# superlna.net
KiCad netlist of a schematic drawn in EAGLE
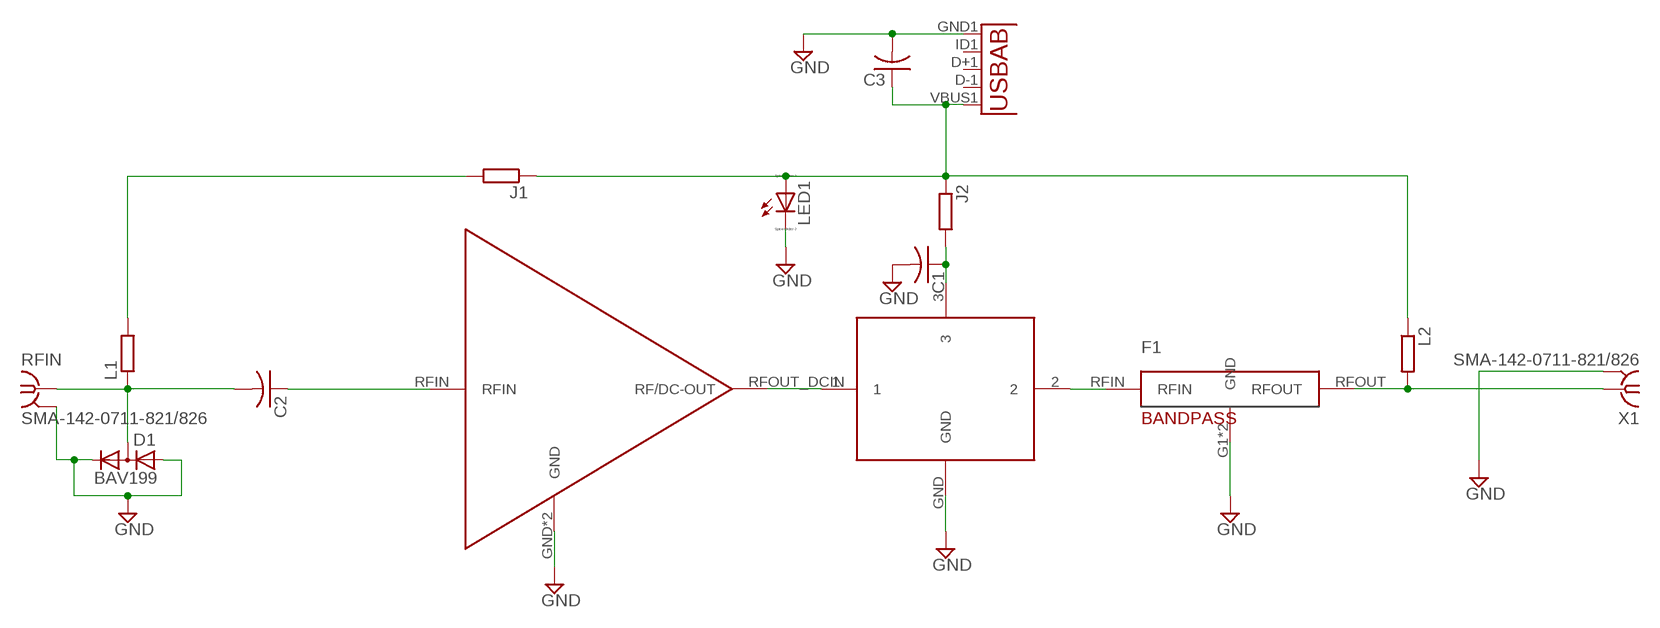
[diagram p0: schematic, sheet 1]

(export (version "E")
  (design (tool "Eeschema 10.0.6"))
  (components
    (comp (ref "C1")
      (value "C-USC0402")
      (footprint "eagle-import:C0402")
      (libsource (lib "eagle-import") (part "C-USC0402"))
    )
    (comp (ref "C2")
      (value "C-USC0402")
      (footprint "eagle-import:C0402")
      (libsource (lib "eagle-import") (part "C-USC0402"))
    )
    (comp (ref "C3")
      (value "C-USC0402")
      (footprint "eagle-import:C0402")
      (libsource (lib "eagle-import") (part "C-USC0402"))
    )
    (comp (ref "D1")
      (value "BAV199")
      (footprint "eagle-import:SOT23")
      (libsource (lib "eagle-import") (part "BAV199"))
    )
    (comp (ref "F1")
      (value "BANDPASS")
      (footprint "eagle-import:FV1206")
      (libsource (lib "eagle-import") (part "BANDPASS"))
    )
    (comp (ref "J1")
      (value "R-EU_R0805")
      (footprint "eagle-import:R0805")
      (libsource (lib "eagle-import") (part "R-EU_R0805"))
    )
    (comp (ref "J2")
      (value "R-EU_R0805")
      (footprint "eagle-import:R0805")
      (libsource (lib "eagle-import") (part "R-EU_R0805"))
    )
    (comp (ref "L1")
      (value "R-EU_R0805")
      (footprint "eagle-import:R0805")
      (libsource (lib "eagle-import") (part "R-EU_R0805"))
    )
    (comp (ref "L2")
      (value "R-EU_R0805")
      (footprint "eagle-import:R0805")
      (libsource (lib "eagle-import") (part "R-EU_R0805"))
    )
    (comp (ref "LED1")
      (value "LED_ESML0603")
      (footprint "eagle-import:LED_SML0603")
      (libsource (lib "eagle-import") (part "LED_ESML0603"))
    )
    (comp (ref "LNA")
      (value "AMP")
      (footprint "eagle-import:SOC-343")
      (libsource (lib "eagle-import") (part "AMP"))
    )
    (comp (ref "POWER")
      (value "USB\"\"")
      (footprint "eagle-import:USB-MICRO-SMD")
      (libsource (lib "eagle-import") (part "USB{dblquote}{dblquote}"))
    )
    (comp (ref "RFIN")
      (value "SMA-142-0711-821/826")
      (footprint "eagle-import:J502-ND-142-0711-821_826")
      (fields (field (name "MF") "JOHNSON COMPONENTS") (field (name "MPN") "142-0711-821"))
      (libsource (lib "eagle-import") (part "SMA-142-0711-821/826"))
    )
    (comp (ref "U1")
      (value "BIASTEE")
      (footprint "eagle-import:GU1414")
      (libsource (lib "eagle-import") (part "BIASTEE"))
    )
    (comp (ref "X1")
      (value "SMA-142-0711-821/826")
      (footprint "eagle-import:J502-ND-142-0711-821_826")
      (fields (field (name "MF") "JOHNSON COMPONENTS") (field (name "MPN") "142-0711-821"))
      (libsource (lib "eagle-import") (part "SMA-142-0711-821/826"))
    )
  )
  (nets
    (net (code "1") (name "GND") (class "Default")
      (node (ref "C1") (pin "2") (pinfunction "2_2") (pintype "passive"))
      (node (ref "C3") (pin "2") (pinfunction "2_2") (pintype "passive"))
      (node (ref "D1") (pin "1") (pinfunction "A_1") (pintype "passive"))
      (node (ref "D1") (pin "2") (pinfunction "C_2") (pintype "passive"))
      (node (ref "F1") (pin "G1") (pinfunction "GND_G1") (pintype "bidirectional"))
      (node (ref "F1") (pin "G2") (pinfunction "GND_G2") (pintype "bidirectional"))
      (node (ref "LED1") (pin "C") (pinfunction "C_C") (pintype "passive"))
      (node (ref "LNA") (pin "GND") (pinfunction "GND_GND") (pintype "bidirectional"))
      (node (ref "LNA") (pin "GND1") (pinfunction "GND_GND1") (pintype "bidirectional"))
      (node (ref "POWER") (pin "GND1") (pinfunction "GND_GND1") (pintype "bidirectional"))
      (node (ref "RFIN") (pin "G@1") (pinfunction "2_G@1") (pintype "passive"))
      (node (ref "RFIN") (pin "G@2") (pinfunction "2_G@2") (pintype "passive"))
      (node (ref "RFIN") (pin "G@3") (pinfunction "2_G@3") (pintype "passive"))
      (node (ref "RFIN") (pin "G@4") (pinfunction "2_G@4") (pintype "passive"))
      (node (ref "U1") (pin "GND") (pinfunction "GND_GND") (pintype "bidirectional"))
      (node (ref "X1") (pin "G@1") (pinfunction "2_G@1") (pintype "passive"))
      (node (ref "X1") (pin "G@2") (pinfunction "2_G@2") (pintype "passive"))
      (node (ref "X1") (pin "G@3") (pinfunction "2_G@3") (pintype "passive"))
      (node (ref "X1") (pin "G@4") (pinfunction "2_G@4") (pintype "passive"))
    )
    (net (code "2") (name "Net-(C1-Pad1)") (class "Default")
      (node (ref "C1") (pin "1") (pinfunction "1_1") (pintype "passive"))
      (node (ref "J2") (pin "2") (pinfunction "2_2") (pintype "passive"))
      (node (ref "U1") (pin "3") (pinfunction "3_3") (pintype "bidirectional"))
    )
    (net (code "3") (name "Net-(C2-Pad1)") (class "Default")
      (node (ref "C2") (pin "1") (pinfunction "1_1") (pintype "passive"))
      (node (ref "LNA") (pin "RFIN") (pinfunction "RFIN_RFIN") (pintype "bidirectional"))
    )
    (net (code "4") (name "Net-(D1-AC)") (class "Default")
      (node (ref "C2") (pin "2") (pinfunction "2_2") (pintype "passive"))
      (node (ref "D1") (pin "3") (pinfunction "AC_3") (pintype "passive"))
      (node (ref "L1") (pin "1") (pinfunction "1_1") (pintype "passive"))
      (node (ref "RFIN") (pin "1") (pinfunction "1_1") (pintype "passive"))
    )
    (net (code "5") (name "Net-(F1-PadRFIN)") (class "Default")
      (node (ref "F1") (pin "RFIN") (pinfunction "RFIN_RFIN") (pintype "bidirectional"))
      (node (ref "U1") (pin "2") (pinfunction "2_2") (pintype "bidirectional"))
    )
    (net (code "6") (name "Net-(F1-PadRFOUT)") (class "Default")
      (node (ref "F1") (pin "RFOUT") (pinfunction "RFOUT_RFOUT") (pintype "bidirectional"))
      (node (ref "L2") (pin "2") (pinfunction "2_2") (pintype "passive"))
      (node (ref "X1") (pin "1") (pinfunction "1_1") (pintype "passive"))
    )
    (net (code "7") (name "Net-(J1-Pad2)") (class "Default")
      (node (ref "J1") (pin "2") (pinfunction "2_2") (pintype "passive"))
      (node (ref "L1") (pin "2") (pinfunction "2_2") (pintype "passive"))
    )
    (net (code "8") (name "Net-(LNA-RF{slash}DC-OUT)") (class "Default")
      (node (ref "LNA") (pin "RFOUT_DCIN") (pinfunction "RF/DC-OUT_RFOUT_DCIN") (pintype "bidirectional"))
      (node (ref "U1") (pin "1") (pinfunction "1_1") (pintype "bidirectional"))
    )
    (net (code "9") (name "Net-(POWER-VBUS)") (class "Default")
      (node (ref "C3") (pin "1") (pinfunction "1_1") (pintype "passive"))
      (node (ref "J1") (pin "1") (pinfunction "1_1") (pintype "passive"))
      (node (ref "J2") (pin "1") (pinfunction "1_1") (pintype "passive"))
      (node (ref "L2") (pin "1") (pinfunction "1_1") (pintype "passive"))
      (node (ref "LED1") (pin "A") (pinfunction "A_A") (pintype "passive"))
      (node (ref "POWER") (pin "VBUS1") (pinfunction "VBUS_VBUS1") (pintype "bidirectional"))
    )
    (net (code "10") (name "unconnected-(POWER-D+-PadD+1)") (class "Default")
      (node (ref "POWER") (pin "D+1") (pinfunction "D+_D+1") (pintype "bidirectional"))
    )
    (net (code "11") (name "unconnected-(POWER-D--PadD-1)") (class "Default")
      (node (ref "POWER") (pin "D-1") (pinfunction "D-_D-1") (pintype "bidirectional"))
    )
    (net (code "12") (name "unconnected-(POWER-USBID-PadID1)") (class "Default")
      (node (ref "POWER") (pin "ID1") (pinfunction "USBID_ID1") (pintype "bidirectional"))
    )
  )
)
